# foot.net
KiCad netlist of a schematic drawn in EAGLE
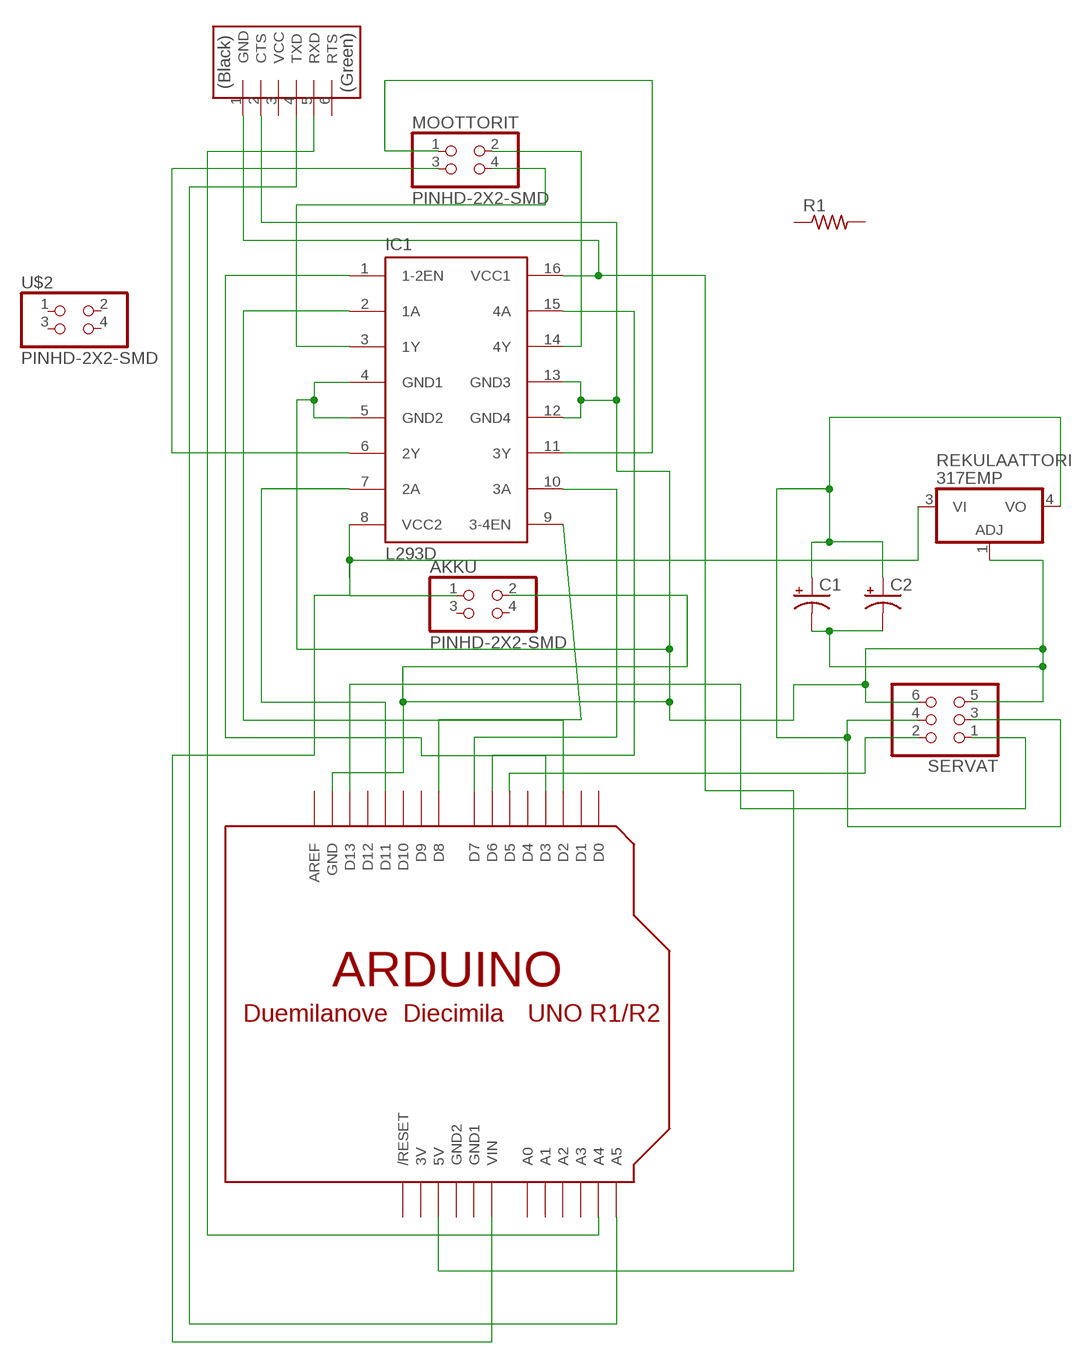
[diagram p0: schematic, sheet 1]

(export (version "E")
  (design (tool "Eeschema 10.0.6"))
  (components
    (comp (ref "AKKU")
      (value "PINHD-2X2-SMD")
      (footprint "eagle-import:2X02SMD")
      (libsource (lib "eagle-import") (part "PINHD-2X2-SMD"))
    )
    (comp (ref "C1")
      (value "CPOL-USE/7260-38W")
      (footprint "eagle-import:E_7260-38W")
      (libsource (lib "eagle-import") (part "CPOL-USE/7260-38W"))
    )
    (comp (ref "C2")
      (value "CPOL-USE/7260-38W")
      (footprint "eagle-import:E_7260-38W")
      (libsource (lib "eagle-import") (part "CPOL-USE/7260-38W"))
    )
    (comp (ref "IC1")
      (value "L293D")
      (footprint "eagle-import:DIL16")
      (libsource (lib "eagle-import") (part "L293D"))
    )
    (comp (ref "MOOTTORIT")
      (value "PINHD-2X2-SMD")
      (footprint "eagle-import:2X02SMD")
      (libsource (lib "eagle-import") (part "PINHD-2X2-SMD"))
    )
    (comp (ref "R1")
      (value "RES-US1206FAB")
      (footprint "eagle-import:R1206FAB")
      (libsource (lib "eagle-import") (part "RES-US1206FAB"))
    )
    (comp (ref "REKULAATTORI")
      (value "317EMP")
      (footprint "eagle-import:SOT223")
      (libsource (lib "eagle-import") (part "317EMP"))
    )
    (comp (ref "SERVAT")
      (value "PINHD-2X3-SMD")
      (footprint "eagle-import:2X03SMD")
      (libsource (lib "eagle-import") (part "PINHD-2X3-SMD"))
    )
    (comp (ref "U$1")
      (value "ARDUINO-BPLACE")
      (footprint "eagle-import:ARDUINO-BPLACE")
      (libsource (lib "eagle-import") (part "ARDUINO-BPLACE"))
    )
    (comp (ref "U$2")
      (value "PINHD-2X2-SMD")
      (footprint "eagle-import:2X02SMD")
      (libsource (lib "eagle-import") (part "PINHD-2X2-SMD"))
    )
    (comp (ref "U$4")
      (value "FTDI-SMD-HEADER")
      (footprint "eagle-import:1X06SMD")
      (libsource (lib "eagle-import") (part "FTDI-SMD-HEADER"))
    )
  )
  (nets
    (net (code "1") (name "/3V") (class "Default")
      (node (ref "U$1") (pin "3V") (pinfunction "3V_3V") (pintype "power_in"))
    )
    (net (code "2") (name "/GND1") (class "Default")
      (node (ref "U$1") (pin "GND1") (pinfunction "GND1_GND1") (pintype "power_in"))
    )
    (net (code "3") (name "/GND2") (class "Default")
      (node (ref "U$1") (pin "GND2") (pinfunction "GND2_GND2") (pintype "power_in"))
    )
    (net (code "4") (name "Net-(IC1-1-2EN)") (class "Default")
      (node (ref "IC1") (pin "1") (pinfunction "1-2EN_1") (pintype "input"))
      (node (ref "U$1") (pin "D3") (pinfunction "D3_D3") (pintype "bidirectional"))
    )
    (net (code "5") (name "Net-(IC1-1A)") (class "Default")
      (node (ref "IC1") (pin "2") (pinfunction "1A_2") (pintype "input"))
      (node (ref "U$1") (pin "D2") (pinfunction "D2_D2") (pintype "bidirectional"))
    )
    (net (code "6") (name "Net-(IC1-1Y)") (class "Default")
      (node (ref "IC1") (pin "3") (pinfunction "1Y_3") (pintype "output"))
      (node (ref "MOOTTORIT") (pin "4") (pinfunction "4_4") (pintype "passive"))
    )
    (net (code "7") (name "Net-(IC1-2A)") (class "Default")
      (node (ref "IC1") (pin "7") (pinfunction "2A_7") (pintype "input"))
      (node (ref "U$1") (pin "D11") (pinfunction "D11_D11") (pintype "bidirectional"))
    )
    (net (code "8") (name "Net-(IC1-2Y)") (class "Default")
      (node (ref "IC1") (pin "6") (pinfunction "2Y_6") (pintype "output"))
      (node (ref "MOOTTORIT") (pin "3") (pinfunction "3_3") (pintype "passive"))
    )
    (net (code "9") (name "Net-(IC1-3-4EN)") (class "Default")
      (node (ref "IC1") (pin "9") (pinfunction "3-4EN_9") (pintype "input"))
      (node (ref "U$1") (pin "D8") (pinfunction "D8_D8") (pintype "bidirectional"))
    )
    (net (code "10") (name "Net-(IC1-3A)") (class "Default")
      (node (ref "IC1") (pin "10") (pinfunction "3A_10") (pintype "input"))
      (node (ref "U$1") (pin "D7") (pinfunction "D7_D7") (pintype "bidirectional"))
    )
    (net (code "11") (name "Net-(IC1-3Y)") (class "Default")
      (node (ref "IC1") (pin "11") (pinfunction "3Y_11") (pintype "output"))
      (node (ref "MOOTTORIT") (pin "1") (pinfunction "1_1") (pintype "passive"))
    )
    (net (code "12") (name "Net-(IC1-4A)") (class "Default")
      (node (ref "IC1") (pin "15") (pinfunction "4A_15") (pintype "input"))
      (node (ref "U$1") (pin "D6") (pinfunction "D6_D6") (pintype "bidirectional"))
    )
    (net (code "13") (name "Net-(IC1-4Y)") (class "Default")
      (node (ref "IC1") (pin "14") (pinfunction "4Y_14") (pintype "output"))
      (node (ref "MOOTTORIT") (pin "2") (pinfunction "2_2") (pintype "passive"))
    )
    (net (code "14") (name "Net-(IC1-GND1)") (class "Default")
      (node (ref "AKKU") (pin "2") (pinfunction "2_2") (pintype "passive"))
      (node (ref "C1") (pin "-") (pinfunction "-_-") (pintype "passive"))
      (node (ref "C2") (pin "-") (pinfunction "-_-") (pintype "passive"))
      (node (ref "IC1") (pin "12") (pinfunction "GND4_12") (pintype "power_in"))
      (node (ref "IC1") (pin "13") (pinfunction "GND3_13") (pintype "power_in"))
      (node (ref "IC1") (pin "4") (pinfunction "GND1_4") (pintype "power_in"))
      (node (ref "IC1") (pin "5") (pinfunction "GND2_5") (pintype "power_in"))
      (node (ref "REKULAATTORI") (pin "1") (pinfunction "ADJ_1") (pintype "input"))
      (node (ref "SERVAT") (pin "5") (pinfunction "5_5") (pintype "passive"))
      (node (ref "SERVAT") (pin "6") (pinfunction "6_6") (pintype "passive"))
      (node (ref "U$1") (pin "GND") (pinfunction "GND_GND") (pintype "power_in"))
      (node (ref "U$4") (pin "2") (pinfunction "CTS_2") (pintype "bidirectional"))
    )
    (net (code "15") (name "Net-(IC1-VCC1)") (class "Default")
      (node (ref "IC1") (pin "16") (pinfunction "VCC1_16") (pintype "power_in"))
      (node (ref "U$1") (pin "5V") (pinfunction "5V_5V") (pintype "power_in"))
      (node (ref "U$4") (pin "1") (pinfunction "GND_1") (pintype "bidirectional"))
    )
    (net (code "16") (name "Net-(IC1-VCC2)") (class "Default")
      (node (ref "AKKU") (pin "1") (pinfunction "1_1") (pintype "passive"))
      (node (ref "IC1") (pin "8") (pinfunction "VCC2_8") (pintype "power_in"))
      (node (ref "REKULAATTORI") (pin "3") (pinfunction "VI_3") (pintype "input"))
      (node (ref "U$1") (pin "VIN") (pinfunction "VIN_VIN") (pintype "power_in"))
    )
    (net (code "17") (name "Net-(REKULAATTORI-VO)") (class "Default")
      (node (ref "C1") (pin "+") (pinfunction "+_+") (pintype "passive"))
      (node (ref "C2") (pin "+") (pinfunction "+_+") (pintype "passive"))
      (node (ref "REKULAATTORI") (pin "4") (pinfunction "VO_4") (pintype "passive"))
      (node (ref "SERVAT") (pin "3") (pinfunction "3_3") (pintype "passive"))
      (node (ref "SERVAT") (pin "4") (pinfunction "4_4") (pintype "passive"))
    )
    (net (code "18") (name "Net-(SERVAT-Pad1)") (class "Default")
      (node (ref "SERVAT") (pin "1") (pinfunction "1_1") (pintype "passive"))
      (node (ref "U$1") (pin "D13") (pinfunction "D13_D13") (pintype "bidirectional"))
    )
    (net (code "19") (name "Net-(SERVAT-Pad2)") (class "Default")
      (node (ref "SERVAT") (pin "2") (pinfunction "2_2") (pintype "passive"))
      (node (ref "U$1") (pin "D5") (pinfunction "D5_D5") (pintype "bidirectional"))
    )
    (net (code "20") (name "Net-(U$4-RXD)") (class "Default")
      (node (ref "U$1") (pin "A4") (pinfunction "A4_A4") (pintype "bidirectional"))
      (node (ref "U$4") (pin "5") (pinfunction "RXD_5") (pintype "bidirectional"))
    )
    (net (code "21") (name "Net-(U$4-TXD)") (class "Default")
      (node (ref "U$1") (pin "A5") (pinfunction "A5_A5") (pintype "bidirectional"))
      (node (ref "U$4") (pin "4") (pinfunction "TXD_4") (pintype "bidirectional"))
    )
    (net (code "22") (name "unconnected-(AKKU-Pad3)") (class "Default")
      (node (ref "AKKU") (pin "3") (pinfunction "3_3") (pintype "passive"))
    )
    (net (code "23") (name "unconnected-(AKKU-Pad4)") (class "Default")
      (node (ref "AKKU") (pin "4") (pinfunction "4_4") (pintype "passive"))
    )
    (net (code "24") (name "unconnected-(R1-Pad1)") (class "Default")
      (node (ref "R1") (pin "1") (pinfunction "1_1") (pintype "passive"))
    )
    (net (code "25") (name "unconnected-(R1-Pad2)") (class "Default")
      (node (ref "R1") (pin "2") (pinfunction "2_2") (pintype "passive"))
    )
    (net (code "26") (name "unconnected-(U$1-PadA0)") (class "Default")
      (node (ref "U$1") (pin "A0") (pinfunction "A0_A0") (pintype "bidirectional"))
    )
    (net (code "27") (name "unconnected-(U$1-PadA1)") (class "Default")
      (node (ref "U$1") (pin "A1") (pinfunction "A1_A1") (pintype "bidirectional"))
    )
    (net (code "28") (name "unconnected-(U$1-PadA2)") (class "Default")
      (node (ref "U$1") (pin "A2") (pinfunction "A2_A2") (pintype "bidirectional"))
    )
    (net (code "29") (name "unconnected-(U$1-PadA3)") (class "Default")
      (node (ref "U$1") (pin "A3") (pinfunction "A3_A3") (pintype "bidirectional"))
    )
    (net (code "30") (name "unconnected-(U$1-PadAREF)") (class "Default")
      (node (ref "U$1") (pin "AREF") (pinfunction "AREF_AREF") (pintype "bidirectional"))
    )
    (net (code "31") (name "unconnected-(U$1-PadD0)") (class "Default")
      (node (ref "U$1") (pin "D0") (pinfunction "D0_D0") (pintype "bidirectional"))
    )
    (net (code "32") (name "unconnected-(U$1-PadD1)") (class "Default")
      (node (ref "U$1") (pin "D1") (pinfunction "D1_D1") (pintype "bidirectional"))
    )
    (net (code "33") (name "unconnected-(U$1-PadD4)") (class "Default")
      (node (ref "U$1") (pin "D4") (pinfunction "D4_D4") (pintype "bidirectional"))
    )
    (net (code "34") (name "unconnected-(U$1-PadD9)") (class "Default")
      (node (ref "U$1") (pin "D9") (pinfunction "D9_D9") (pintype "bidirectional"))
    )
    (net (code "35") (name "unconnected-(U$1-PadD10)") (class "Default")
      (node (ref "U$1") (pin "D10") (pinfunction "D10_D10") (pintype "bidirectional"))
    )
    (net (code "36") (name "unconnected-(U$1-PadD12)") (class "Default")
      (node (ref "U$1") (pin "D12") (pinfunction "D12_D12") (pintype "bidirectional"))
    )
    (net (code "37") (name "unconnected-(U$1-{slash}RESET-PadRESET)") (class "Default")
      (node (ref "U$1") (pin "RESET") (pinfunction "/RESET_RESET") (pintype "bidirectional"))
    )
    (net (code "38") (name "unconnected-(U$2-Pad1)") (class "Default")
      (node (ref "U$2") (pin "1") (pinfunction "1_1") (pintype "passive"))
    )
    (net (code "39") (name "unconnected-(U$2-Pad2)") (class "Default")
      (node (ref "U$2") (pin "2") (pinfunction "2_2") (pintype "passive"))
    )
    (net (code "40") (name "unconnected-(U$2-Pad3)") (class "Default")
      (node (ref "U$2") (pin "3") (pinfunction "3_3") (pintype "passive"))
    )
    (net (code "41") (name "unconnected-(U$2-Pad4)") (class "Default")
      (node (ref "U$2") (pin "4") (pinfunction "4_4") (pintype "passive"))
    )
    (net (code "42") (name "unconnected-(U$4-RTS-Pad6)") (class "Default")
      (node (ref "U$4") (pin "6") (pinfunction "RTS_6") (pintype "bidirectional"))
    )
    (net (code "43") (name "unconnected-(U$4-VCC-Pad3)") (class "Default")
      (node (ref "U$4") (pin "3") (pinfunction "VCC_3") (pintype "bidirectional"))
    )
  )
)
